# ESP32.net
KiCad netlist of a schematic drawn in Altium Designer
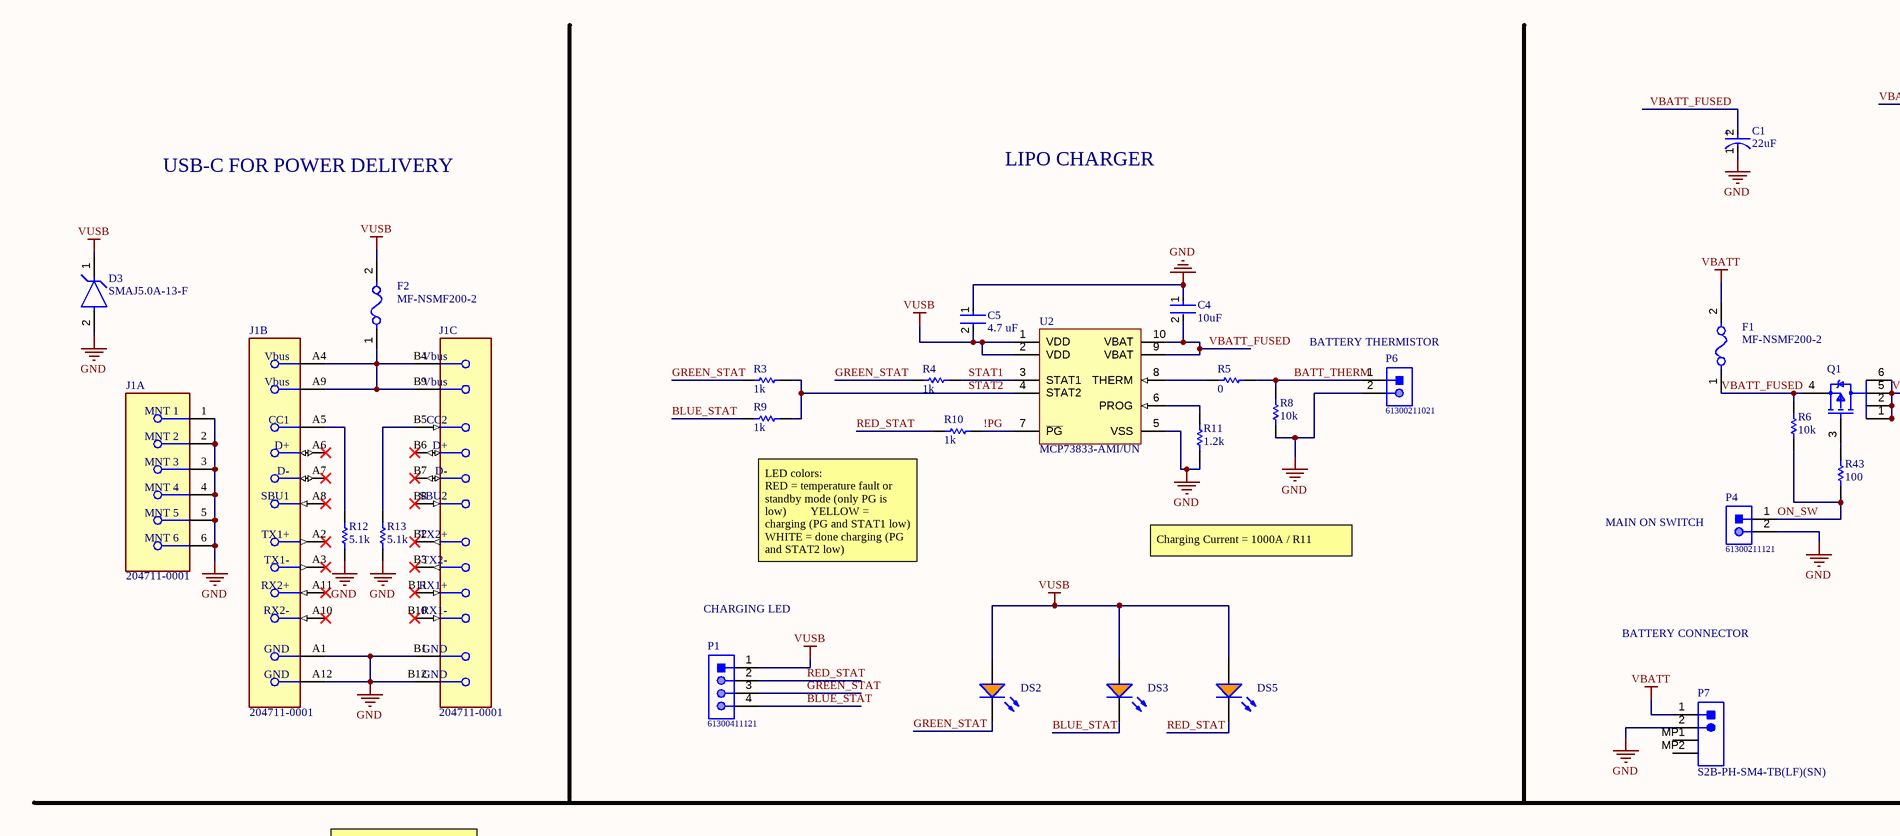
[diagram p0: ESP32.SchDoc, top left]
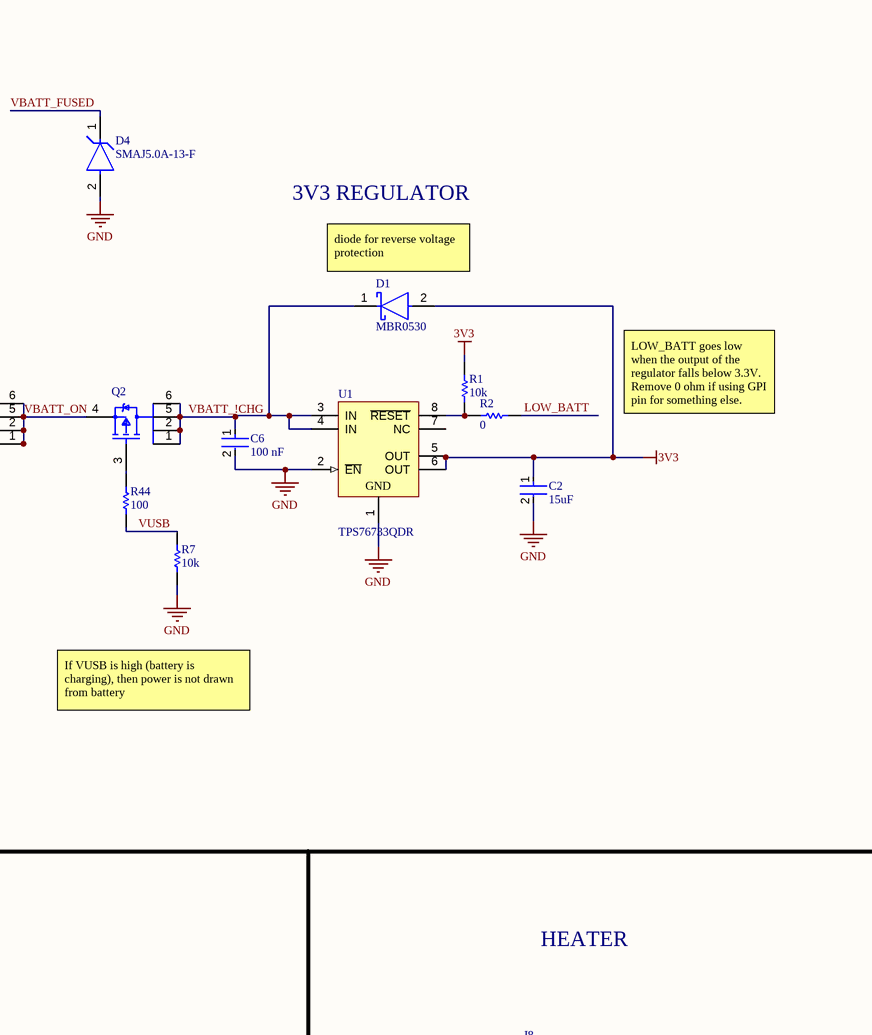
[diagram p1: ESP32.SchDoc, top right]
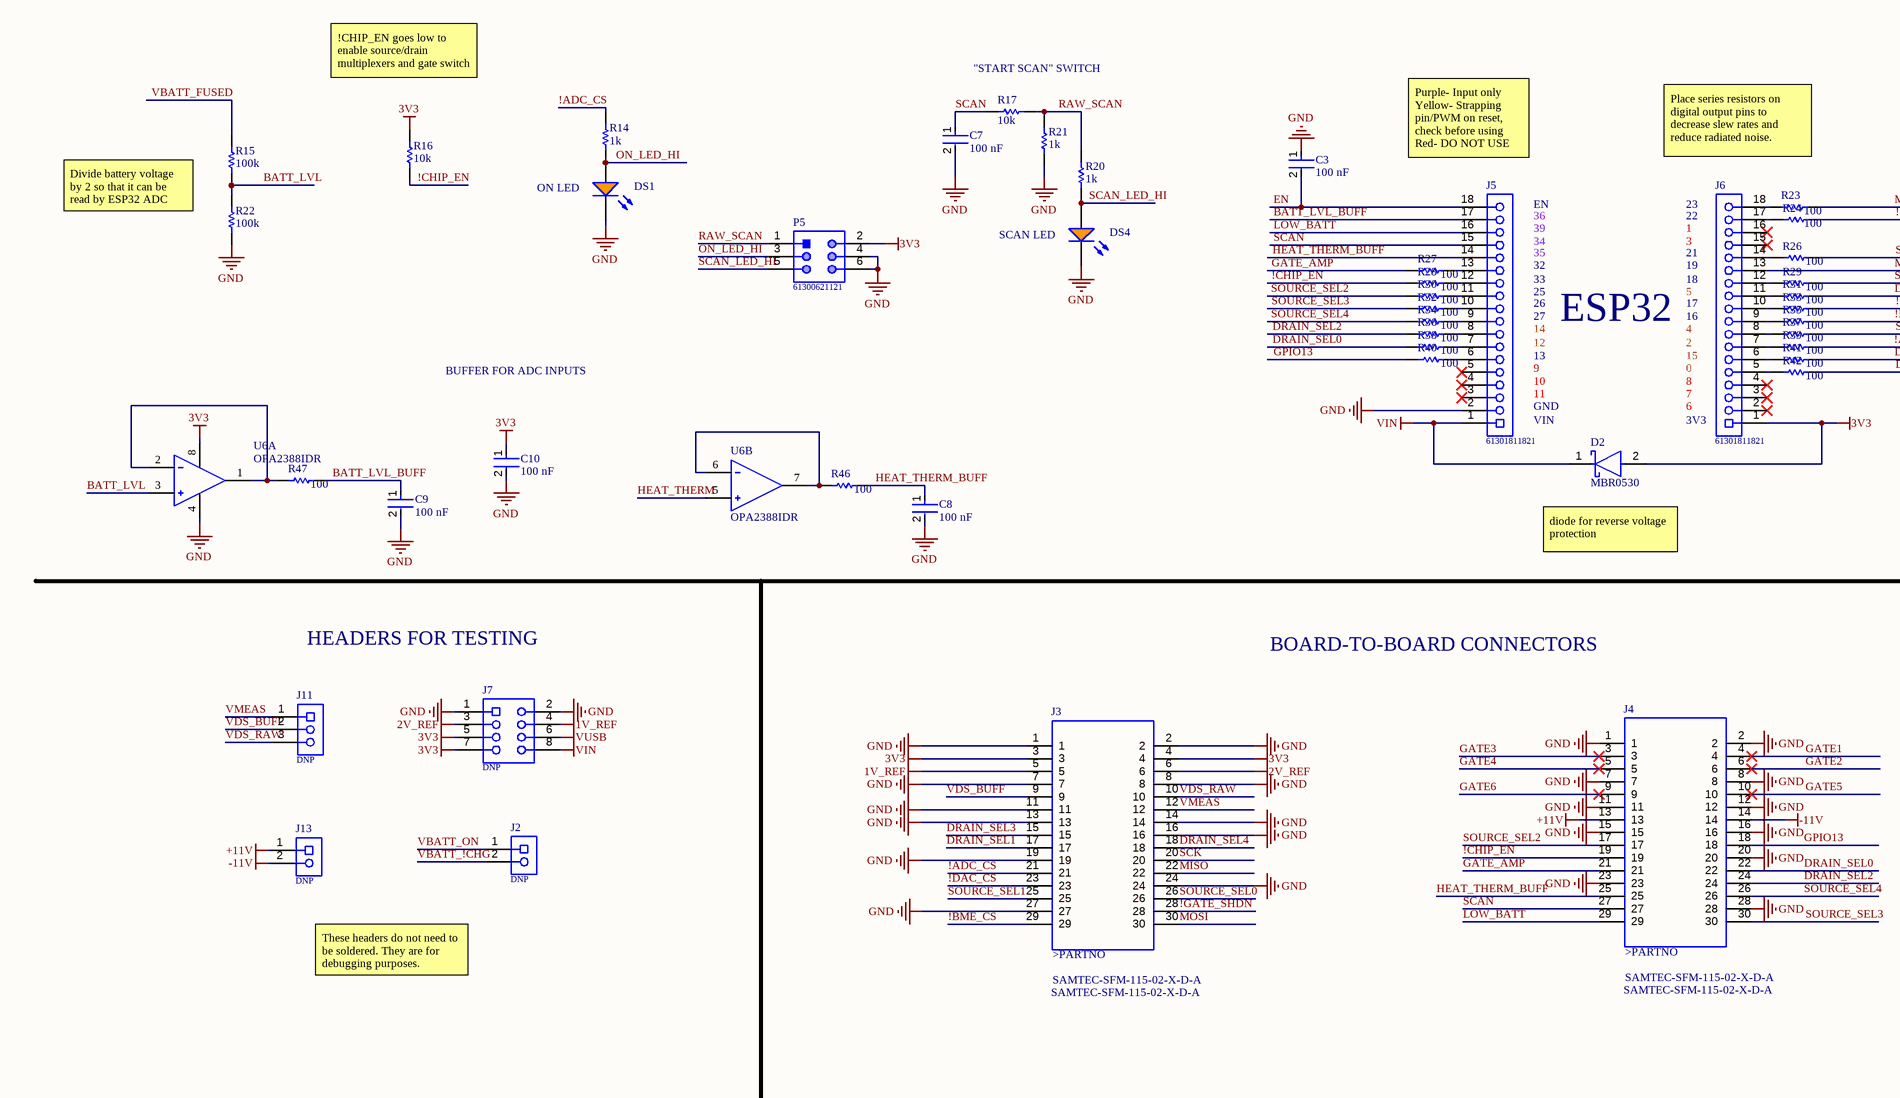
[diagram p2: ESP32.SchDoc, bottom left]
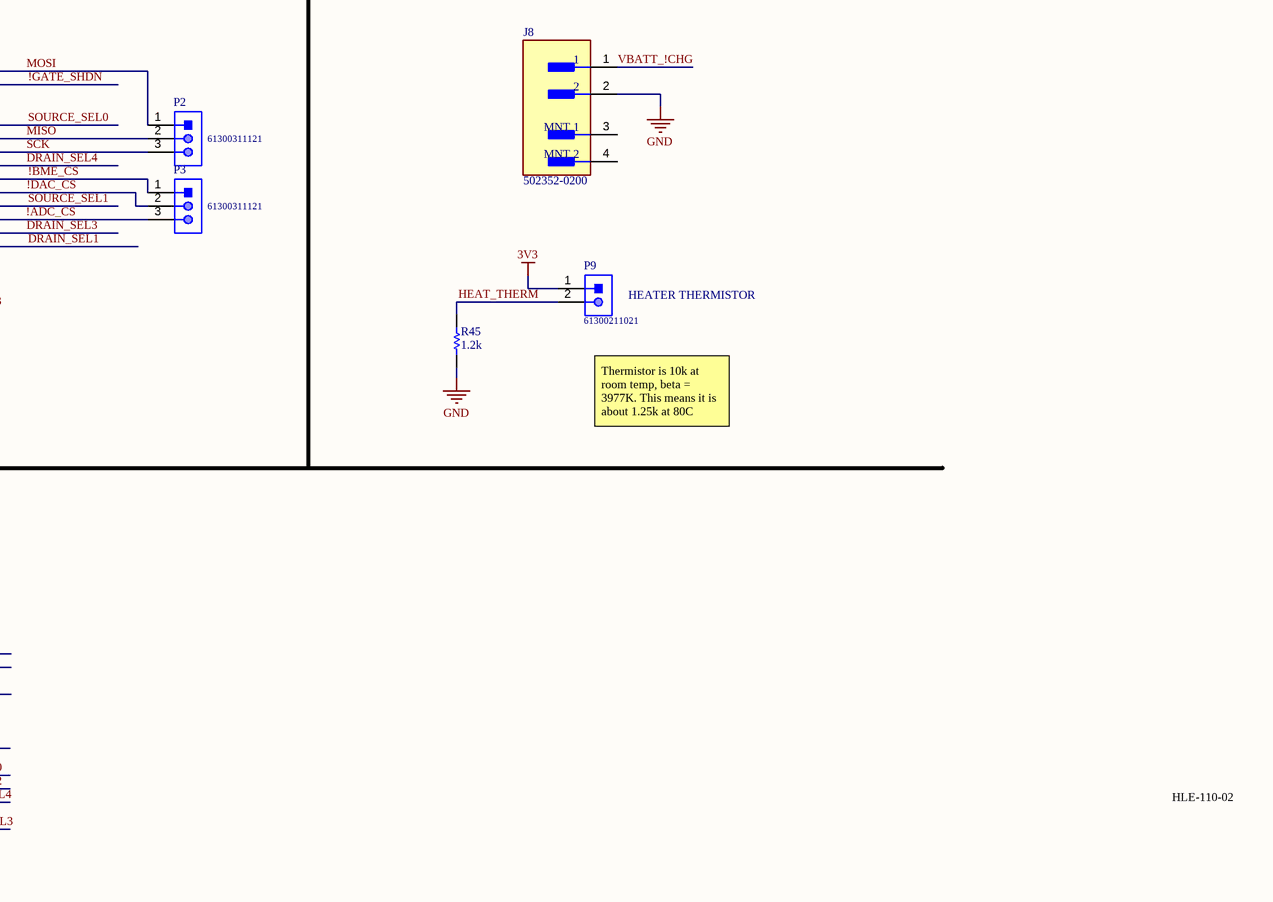
[diagram p3: ESP32.SchDoc, bottom right]

(export (version "E")
  (design (tool "Eeschema 10.0.6"))
  (components
    (comp (ref "C1")
      (value "22uF")
      (footprint "FP-FKC-MFG")
      (description "CAP ALUM 22UF 20% 35V SMD")
      (fields (field (name "VOLTAGE") "35V") (field (name "TOLERANCE") "20%"))
      (libsource (lib "Altium Content Vault") (part "a00bbbee19879c290e62620ae7e47b1"))
    )
    (comp (ref "C2")
      (value "15uF")
      (footprint "FP-C2012-125-0_2-MFG")
      (description "Multilayer Ceramic Capacitors 15μF ±20% 25V JB SMD 0805")
      (fields (field (name "TOLERANCE") "20%"))
      (libsource (lib "Altium Content Vault") (part "b4654b650e69147ec39a6b967a45e02"))
    )
    (comp (ref "C3")
      (value "100 nF")
      (footprint "FP-C0805C-DN-MFG")
      (description "CAP CER 0.1UF 50V X7R 0805")
      (fields
        (field (name "MANUFACTURER PART NUMBER") "C0805C104K5RACTU")
        (field (name "MANUFACTURER") "KEMET")
      )
      (libsource (lib "Altium Content Vault") (part "b4654b650e69147ec39a6b967a45e02"))
    )
    (comp (ref "C4")
      (value "10uF")
      (footprint "FP-GRM21B-0_1-IPC_C")
      (description "Chip Multilayer Ceramic Capacitors for General Purpose, 0805, 10uF, X5R, 15%, 10%, 16V")
      (fields (field (name "TOLERANCE") "10%") (field (name "VOLTAGE") "16V"))
      (libsource (lib "Altium Content Vault") (part "b4654b650e69147ec39a6b967a45e02"))
    )
    (comp (ref "C5")
      (value "4.7 uF")
      (footprint "FP-C0805C475K3PACTU-MFG")
      (description "CAP CER 4.7UF 25V X5R 0805")
      (fields (field (name "TOLERANCE") "10%") (field (name "VOLTAGE") "25V"))
      (libsource (lib "Altium Content Vault") (part "02cd4be3c70576c341d710602a673aa"))
    )
    (comp (ref "C6")
      (value "100 nF")
      (footprint "FP-C0805C-DN-MFG")
      (description "CAP CER 0.1UF 50V X7R 0805")
      (fields
        (field (name "MANUFACTURER PART NUMBER") "C0805C104K5RACTU")
        (field (name "MANUFACTURER") "KEMET")
      )
      (libsource (lib "Altium Content Vault") (part "b4654b650e69147ec39a6b967a45e02"))
    )
    (comp (ref "C7")
      (value "100 nF")
      (footprint "FP-C0805C-DN-MFG")
      (description "CAP CER 0.1UF 50V X7R 0805")
      (fields
        (field (name "MANUFACTURER PART NUMBER") "C0805C104K5RACTU")
        (field (name "MANUFACTURER") "KEMET")
      )
      (libsource (lib "Altium Content Vault") (part "b4654b650e69147ec39a6b967a45e02"))
    )
    (comp (ref "C8")
      (value "100 nF")
      (footprint "FP-C0805C-DN-MFG")
      (description "CAP CER 0.1UF 50V X7R 0805")
      (fields
        (field (name "MANUFACTURER PART NUMBER") "C0805C104K5RACTU")
        (field (name "MANUFACTURER") "KEMET")
      )
      (libsource (lib "Altium Content Vault") (part "b4654b650e69147ec39a6b967a45e02"))
    )
    (comp (ref "C9")
      (value "100 nF")
      (footprint "FP-C0805C-DN-MFG")
      (description "CAP CER 0.1UF 50V X7R 0805")
      (fields
        (field (name "MANUFACTURER PART NUMBER") "C0805C104K5RACTU")
        (field (name "MANUFACTURER") "KEMET")
      )
      (libsource (lib "Altium Content Vault") (part "b4654b650e69147ec39a6b967a45e02"))
    )
    (comp (ref "C10")
      (value "100 nF")
      (footprint "FP-C0805C-DN-MFG")
      (description "CAP CER 0.1UF 50V X7R 0805")
      (fields
        (field (name "MANUFACTURER PART NUMBER") "C0805C104K5RACTU")
        (field (name "MANUFACTURER") "KEMET")
      )
      (libsource (lib "Altium Content Vault") (part "b4654b650e69147ec39a6b967a45e02"))
    )
    (comp (ref "D1")
      (value "MBR0530")
      (footprint "FP-425-04-MFG")
      (description "DIODE SCHOTTKY 30V 500MA SOD123")
      (libsource (lib "Altium Content Vault") (part "1d6ec82d83fb6aee721767c19dac4b9"))
    )
    (comp (ref "D2")
      (value "MBR0530")
      (footprint "FP-425-04-MFG")
      (description "DIODE SCHOTTKY 30V 500MA SOD123")
      (libsource (lib "Altium Content Vault") (part "1d6ec82d83fb6aee721767c19dac4b9"))
    )
    (comp (ref "D3")
      (value "SMAJ5.0A-13-F")
      (footprint "FP-SMA-MFG")
      (description "TVS DIODE 5V 9.2V SMA")
      (fields
        (field (name "MANUFACTURER") "Diodes Inc.")
        (field (name "OCTOPART") "https://octopart.com/smaj5.0a-13-f-diodes+inc.-350158")
      )
      (libsource (lib "Altium Content Vault") (part "f813f71cba58e380607f5dd3caf9714"))
    )
    (comp (ref "D4")
      (value "SMAJ5.0A-13-F")
      (footprint "FP-SMA-MFG")
      (description "TVS DIODE 5V 9.2V SMA")
      (fields
        (field (name "MANUFACTURER") "Diodes Inc.")
        (field (name "OCTOPART") "https://octopart.com/smaj5.0a-13-f-diodes+inc.-350158")
      )
      (libsource (lib "Altium Content Vault") (part "f813f71cba58e380607f5dd3caf9714"))
    )
    (comp (ref "DS1")
      (value "HSMD-C170")
      (footprint "AVAG-HSMX-C170_V")
      (description "LED Uni-Color Orange, 52 mW, 20 mA, -40 to 85 degC, 2-Pin SMD, RoHS, Tape and Reel")
      (fields (field (name "MANUFACTURER") "Avago"))
      (libsource (lib "Altium Content Vault") (part "LED-ORANGE-AK-2"))
    )
    (comp (ref "DS2")
      (value "HSMD-C170")
      (footprint "AVAG-HSMX-C170_V")
      (description "LED Uni-Color Orange, 52 mW, 20 mA, -40 to 85 degC, 2-Pin SMD, RoHS, Tape and Reel")
      (fields (field (name "MANUFACTURER") "Avago"))
      (libsource (lib "Altium Content Vault") (part "LED-ORANGE-AK-2"))
    )
    (comp (ref "DS3")
      (value "HSMD-C170")
      (footprint "AVAG-HSMX-C170_V")
      (description "LED Uni-Color Orange, 52 mW, 20 mA, -40 to 85 degC, 2-Pin SMD, RoHS, Tape and Reel")
      (fields (field (name "MANUFACTURER") "Avago"))
      (libsource (lib "Altium Content Vault") (part "LED-ORANGE-AK-2"))
    )
    (comp (ref "DS4")
      (value "HSMD-C170")
      (footprint "AVAG-HSMX-C170_V")
      (description "LED Uni-Color Orange, 52 mW, 20 mA, -40 to 85 degC, 2-Pin SMD, RoHS, Tape and Reel")
      (fields (field (name "MANUFACTURER") "Avago"))
      (libsource (lib "Altium Content Vault") (part "LED-ORANGE-AK-2"))
    )
    (comp (ref "DS5")
      (value "HSMD-C170")
      (footprint "AVAG-HSMX-C170_V")
      (description "LED Uni-Color Orange, 52 mW, 20 mA, -40 to 85 degC, 2-Pin SMD, RoHS, Tape and Reel")
      (fields (field (name "MANUFACTURER") "Avago"))
      (libsource (lib "Altium Content Vault") (part "LED-ORANGE-AK-2"))
    )
    (comp (ref "F1")
      (value "MF-NSMF200-2")
      (footprint "FP-MF-NSMF200-2-MFG")
      (description "PTC RESET FUSE 6V 2A 1206")
      (fields
        (field (name "MANUFACTURER") "Bourns Inc.")
        (field (name "OCTOPART") "https://octopart.com/mf-nsmf200-2-bourns-90790")
      )
      (libsource (lib "Altium Content Vault") (part "5bcf9b9f640e542cf0359d10258e979"))
    )
    (comp (ref "F2")
      (value "MF-NSMF200-2")
      (footprint "FP-MF-NSMF200-2-MFG")
      (description "PTC RESET FUSE 6V 2A 1206")
      (fields
        (field (name "MANUFACTURER") "Bourns Inc.")
        (field (name "OCTOPART") "https://octopart.com/mf-nsmf200-2-bourns-90790")
      )
      (libsource (lib "Altium Content Vault") (part "5bcf9b9f640e542cf0359d10258e979"))
    )
    (comp (ref "J1")
      (value "204711-0001")
      (footprint "FP-204711-0001-MFG")
      (description "USB VERTICAL TYPE C 3.1")
      (libsource (lib "Altium Content Vault") (part "b295db2379a271355c8cebff2fed634"))
    )
    (comp (ref "J2")
      (value "DNP")
      (footprint "61300211821")
      (description "THT Vertical Socket Header WR-PHD, Pitch 2.54 mm, Single Row, 2 pins")
      (fields
        (field (name "PART NUMBER") "61300211821")
        (field (name "MANUFACTURER") "Wurth Elektronik")
        (field (name "PUBLISHER") "WurthElektronik")
      )
      (libsource (lib "Altium Content Vault") (part "WE-CN-1P-F-R2"))
    )
    (comp (ref "J3")
      (value "SAMTEC-SFM-115-02-X-D-A")
      (footprint "SAMTEC-SFM-115-02-X-D-A:SAMTEC-SFM-115-02-X-D-A")
      (fields (field (name "MF") "Samtec Inc."))
      (libsource (lib "SAMTEC-SFM-115-02-X-D-A") (part "SAMTEC-SFM-115-02-X-D-A"))
    )
    (comp (ref "J4")
      (value "SAMTEC-SFM-115-02-X-D-A")
      (footprint "SAMTEC-SFM-115-02-X-D-A:SAMTEC-SFM-115-02-X-D-A")
      (fields (field (name "MF") "Samtec Inc."))
      (libsource (lib "SAMTEC-SFM-115-02-X-D-A") (part "SAMTEC-SFM-115-02-X-D-A"))
    )
    (comp (ref "J5")
      (value "61301811821")
      (footprint "61301811821")
      (description "THT Vertical Socket Header WR-PHD, Pitch 2.54 mm, Single Row, 18 pins")
      (fields (field (name "MANUFACTURER") "Wurth Elektronik") (field (name "PUBLISHER") "WurthElektronik"))
      (libsource (lib "Altium Content Vault") (part "WE-CN-1P-F-R18"))
    )
    (comp (ref "J6")
      (value "61301811821")
      (footprint "61301811821")
      (description "THT Vertical Socket Header WR-PHD, Pitch 2.54 mm, Single Row, 18 pins")
      (fields (field (name "MANUFACTURER") "Wurth Elektronik") (field (name "PUBLISHER") "WurthElektronik"))
      (libsource (lib "") (part "WE-CN-1P-F-R18_1"))
    )
    (comp (ref "J7")
      (value "DNP")
      (footprint "61300821821")
      (description "THT Vertical Socket Header WR-PHD, Pitch 2.54 mm, Dual Row, 8 pins")
      (fields
        (field (name "MANUFACTURER") "Wurth Elektronik")
        (field (name "PART NUMBER") "61300821821")
        (field (name "PUBLISHER") "WurthElektronik")
      )
      (libsource (lib "Altium Content Vault") (part "WE-CN-2P-F-R8"))
    )
    (comp (ref "J8")
      (value "502352-0200")
      (footprint "FP-502352-0200-MFG")
      (description "CONN HEADER SMD R/A 2POS 2MM")
      (fields
        (field (name "MANUFACTURER") "Molex")
        (field (name "OCTOPART") "https://octopart.com/502352-0200-molex-9519058")
      )
      (libsource (lib "Altium Content Vault") (part "029478cb6d4f2fad0cd2a245525ee6d"))
    )
    (comp (ref "J11")
      (value "DNP")
      (footprint "61300311821")
      (description "THT Vertical Socket Header WR-PHD, Pitch 2.54 mm, Single Row, 3 pins")
      (fields
        (field (name "MANUFACTURER") "Wurth Elektronik")
        (field (name "PART NUMBER") "61300311821")
        (field (name "PUBLISHER") "WurthElektronik")
      )
      (libsource (lib "Altium Content Vault") (part "WE-CN-1P-F-R3"))
    )
    (comp (ref "J13")
      (value "DNP")
      (footprint "61300211821")
      (description "THT Vertical Socket Header WR-PHD, Pitch 2.54 mm, Single Row, 2 pins")
      (fields
        (field (name "PART NUMBER") "61300211821")
        (field (name "MANUFACTURER") "Wurth Elektronik")
        (field (name "PUBLISHER") "WurthElektronik")
      )
      (libsource (lib "Altium Content Vault") (part "WE-CN-1P-F-R2"))
    )
    (comp (ref "P1")
      (value "61300411121")
      (footprint "61300411121")
      (description "THT Vertical Pin Header WR-PHD, Pitch 2.54 mm, Single Row, 4 pins")
      (fields (field (name "MANUFACTURER") "Wurth Elektronik") (field (name "PUBLISHER") "WurthElektronik"))
      (libsource (lib "Altium Content Vault") (part "WE-CN-1P-M-R4"))
    )
    (comp (ref "P2")
      (value "61300311121")
      (footprint "61300311121")
      (description "THT Vertical Pin Header WR-PHD, Pitch 2.54 mm, Single Row, 3 pins")
      (fields (field (name "MANUFACTURER") "Wurth Elektronik") (field (name "PUBLISHER") "WurthElektronik"))
      (libsource (lib "Altium Content Vault") (part "WE-CN-1P-M-R3"))
    )
    (comp (ref "P3")
      (value "61300311121")
      (footprint "61300311121")
      (description "THT Vertical Pin Header WR-PHD, Pitch 2.54 mm, Single Row, 3 pins")
      (fields (field (name "MANUFACTURER") "Wurth Elektronik") (field (name "PUBLISHER") "WurthElektronik"))
      (libsource (lib "Altium Content Vault") (part "WE-CN-1P-M-R3"))
    )
    (comp (ref "P4")
      (value "61300211121")
      (footprint "61300211121")
      (description "THT Vertical Pin Header WR-PHD, Pitch 2.54 mm, Single Row, 2 pins")
      (fields (field (name "MANUFACTURER") "Wurth Elektronik") (field (name "PUBLISHER") "WurthElektronik"))
      (libsource (lib "") (part "WE-CN-1P-M-R2_1"))
    )
    (comp (ref "P5")
      (value "61300621121")
      (footprint "61300621121")
      (description "THT Vertical Pin Header WR-PHD, Pitch 2.54 mm, Dual Row, 6 pins")
      (fields (field (name "MANUFACTURER") "Wurth Elektronik") (field (name "PUBLISHER") "WurthElektronik"))
      (libsource (lib "Altium Content Vault") (part "WE-CN-2P-M-R6"))
    )
    (comp (ref "P6")
      (value "61300211021")
      (footprint "61300211021")
      (description "THT Angled Pin Header WR-PHD, Pitch 2.54 mm, Single Row, 2 pins")
      (fields (field (name "MANUFACTURER") "Wurth Elektronik") (field (name "PUBLISHER") "WurthElektronik"))
      (libsource (lib "Altium Content Vault") (part "WE-CN-1P-M-R2"))
    )
    (comp (ref "P7")
      (value "S2B-PH-SM4-TB(LF)(SN)")
      (footprint "JST- S2B-PH-SM4-TB(LF)(SN)-2_V")
      (description "Male Header, Pitch 2 mm, 1 x 2 Position, Height 5.5 mm, -25 to 85 degC, RoHS, Tape and Reel")
      (libsource (lib "Altium Content Vault") (part "CN-1P-2M-R2"))
    )
    (comp (ref "P9")
      (value "61300211021")
      (footprint "61300211021")
      (description "THT Angled Pin Header WR-PHD, Pitch 2.54 mm, Single Row, 2 pins")
      (fields (field (name "MANUFACTURER") "Wurth Elektronik") (field (name "PUBLISHER") "WurthElektronik"))
      (libsource (lib "Altium Content Vault") (part "WE-CN-1P-M-R2"))
    )
    (comp (ref "Q1")
      (value "SI3493DDV-T1-GE3")
      (footprint "FP-C-06593-MFG")
      (description "MOSFET P-CHANNEL 20V 8A 6TSOP")
      (fields
        (field (name "MANUFACTURER") "Vishay")
        (field (name "OCTOPART") "https://octopart.com/si3493ddv-t1-ge3-vishay-81014282")
      )
      (libsource (lib "Altium Content Vault") (part "cb80e2443ef6eac25cf60ecf9c1abdf"))
    )
    (comp (ref "Q2")
      (value "SI3493DDV-T1-GE3")
      (footprint "FP-C-06593-MFG")
      (description "MOSFET P-CHANNEL 20V 8A 6TSOP")
      (fields
        (field (name "MANUFACTURER") "Vishay")
        (field (name "OCTOPART") "https://octopart.com/si3493ddv-t1-ge3-vishay-81014282")
      )
      (libsource (lib "Altium Content Vault") (part "cb80e2443ef6eac25cf60ecf9c1abdf"))
    )
    (comp (ref "R1")
      (value "10k")
      (footprint "RESC2013X60X35NL10T20")
      (description "Chip Resistor, 10 KOhm, +/- 1%, 0.125 W, -55 to 155 degC, 0805 (2012 Metric), RoHS, Tape and Reel")
      (fields (field (name "MANUFACTURER") "Yageo"))
      (libsource (lib "Altium Content Vault") (part "RES-2"))
    )
    (comp (ref "R2")
      (value "0")
      (footprint "RESC2013X50X30LL20T20")
      (fields (field (name "MANUFACTURER") "Vishay Dale") (field (name "PART NUMBER") "CRCW08050000Z0EA"))
      (libsource (lib "Altium Content Vault") (part "RES"))
    )
    (comp (ref "R3")
      (value "1k")
      (footprint "RESC2013X55X40LL15T20")
      (description "TNPW08051K00BEEN")
      (fields (field (name "MANUFACTURER") "Vishay Dale"))
      (libsource (lib "Altium Content Vault") (part "RES"))
    )
    (comp (ref "R4")
      (value "1k")
      (footprint "RESC2013X55X40LL15T20")
      (description "TNPW08051K00BEEN")
      (fields (field (name "MANUFACTURER") "Vishay Dale"))
      (libsource (lib "Altium Content Vault") (part "RES"))
    )
    (comp (ref "R5")
      (value "0")
      (footprint "RESC2013X50X30LL20T20")
      (fields (field (name "MANUFACTURER") "Vishay Dale") (field (name "PART NUMBER") "CRCW08050000Z0EA"))
      (libsource (lib "Altium Content Vault") (part "RES"))
    )
    (comp (ref "R6")
      (value "10k")
      (footprint "RESC2013X60X35NL10T20")
      (description "Chip Resistor, 10 KOhm, +/- 1%, 0.125 W, -55 to 155 degC, 0805 (2012 Metric), RoHS, Tape and Reel")
      (fields (field (name "MANUFACTURER") "Yageo"))
      (libsource (lib "Altium Content Vault") (part "RES-2"))
    )
    (comp (ref "R7")
      (value "10k")
      (footprint "RESC2013X60X35NL10T20")
      (description "Chip Resistor, 10 KOhm, +/- 1%, 0.125 W, -55 to 155 degC, 0805 (2012 Metric), RoHS, Tape and Reel")
      (fields (field (name "MANUFACTURER") "Yageo"))
      (libsource (lib "Altium Content Vault") (part "RES-2"))
    )
    (comp (ref "R8")
      (value "10k")
      (footprint "RESC2013X60X35NL10T20")
      (description "Chip Resistor, 10 KOhm, +/- 1%, 0.125 W, -55 to 155 degC, 0805 (2012 Metric), RoHS, Tape and Reel")
      (fields (field (name "MANUFACTURER") "Yageo"))
      (libsource (lib "Altium Content Vault") (part "RES-2"))
    )
    (comp (ref "R9")
      (value "1k")
      (footprint "RESC2013X55X40LL15T20")
      (description "TNPW08051K00BEEN")
      (fields (field (name "MANUFACTURER") "Vishay Dale"))
      (libsource (lib "Altium Content Vault") (part "RES"))
    )
    (comp (ref "R10")
      (value "1k")
      (footprint "RESC2013X55X40LL15T20")
      (description "TNPW08051K00BEEN")
      (fields (field (name "MANUFACTURER") "Vishay Dale"))
      (libsource (lib "Altium Content Vault") (part "RES"))
    )
    (comp (ref "R11")
      (value "1.2k")
      (footprint "RESC2013X60X40LL20T25")
      (description "precision 0.1%")
      (fields (field (name "MANUFACTURER") "Panasonic") (field (name "PART NUMBER") "ERA6AEB122V"))
      (libsource (lib "Altium Content Vault") (part "RES"))
    )
    (comp (ref "R12")
      (value "5.1k")
      (footprint "RESC2013X60X40LL20T25")
      (fields (field (name "MANUFACTURER") "Panasonic") (field (name "PART NUMBER") "ERA6AEB512V"))
      (libsource (lib "Altium Content Vault") (part "RES"))
    )
    (comp (ref "R13")
      (value "5.1k")
      (footprint "RESC2013X60X40LL20T25")
      (fields (field (name "MANUFACTURER") "Panasonic") (field (name "PART NUMBER") "ERA6AEB512V"))
      (libsource (lib "Altium Content Vault") (part "RES"))
    )
    (comp (ref "R14")
      (value "1k")
      (footprint "RESC2013X55X40LL15T20")
      (description "TNPW08051K00BEEN")
      (fields (field (name "MANUFACTURER") "Vishay Dale"))
      (libsource (lib "Altium Content Vault") (part "RES"))
    )
    (comp (ref "R15")
      (value "100k")
      (footprint "RESC2013X55X40LL15T20")
      (description "precision 0.1%")
      (fields (field (name "PART NUMBER") "TNPW0805100KBEEA") (field (name "MANUFACTURER") "Vishay Dale"))
      (libsource (lib "Altium Content Vault") (part "RES"))
    )
    (comp (ref "R16")
      (value "10k")
      (footprint "RESC2013X60X35NL10T20")
      (description "Chip Resistor, 10 KOhm, +/- 1%, 0.125 W, -55 to 155 degC, 0805 (2012 Metric), RoHS, Tape and Reel")
      (fields (field (name "MANUFACTURER") "Yageo"))
      (libsource (lib "Altium Content Vault") (part "RES-2"))
    )
    (comp (ref "R17")
      (value "10k")
      (footprint "RESC2013X60X35NL10T20")
      (description "Chip Resistor, 10 KOhm, +/- 1%, 0.125 W, -55 to 155 degC, 0805 (2012 Metric), RoHS, Tape and Reel")
      (fields (field (name "MANUFACTURER") "Yageo"))
      (libsource (lib "Altium Content Vault") (part "RES-2"))
    )
    (comp (ref "R20")
      (value "1k")
      (footprint "RESC2013X55X40LL15T20")
      (description "TNPW08051K00BEEN")
      (fields (field (name "MANUFACTURER") "Vishay Dale"))
      (libsource (lib "Altium Content Vault") (part "RES"))
    )
    (comp (ref "R21")
      (value "1k")
      (footprint "RESC2013X55X40LL15T20")
      (description "TNPW08051K00BEEN")
      (fields (field (name "MANUFACTURER") "Vishay Dale"))
      (libsource (lib "Altium Content Vault") (part "RES"))
    )
    (comp (ref "R22")
      (value "100k")
      (footprint "RESC2013X55X40LL15T20")
      (description "precision 0.1%")
      (fields (field (name "PART NUMBER") "TNPW0805100KBEEA") (field (name "MANUFACTURER") "Vishay Dale"))
      (libsource (lib "Altium Content Vault") (part "RES"))
    )
    (comp (ref "R23")
      (value "100")
      (footprint "RESC2013X50X30LL20T20")
      (fields (field (name "MANUFACTURER") "Vishay Dale") (field (name "PART NUMBER") "CRCW0805100RFKEA"))
      (libsource (lib "Altium Content Vault") (part "RES"))
    )
    (comp (ref "R24")
      (value "100")
      (footprint "RESC2013X50X30LL20T20")
      (fields (field (name "MANUFACTURER") "Vishay Dale") (field (name "PART NUMBER") "CRCW0805100RFKEA"))
      (libsource (lib "Altium Content Vault") (part "RES"))
    )
    (comp (ref "R26")
      (value "100")
      (footprint "RESC2013X50X30LL20T20")
      (fields (field (name "MANUFACTURER") "Vishay Dale") (field (name "PART NUMBER") "CRCW0805100RFKEA"))
      (libsource (lib "Altium Content Vault") (part "RES"))
    )
    (comp (ref "R27")
      (value "100")
      (footprint "RESC2013X50X30LL20T20")
      (fields (field (name "MANUFACTURER") "Vishay Dale") (field (name "PART NUMBER") "CRCW0805100RFKEA"))
      (libsource (lib "Altium Content Vault") (part "RES"))
    )
    (comp (ref "R28")
      (value "100")
      (footprint "RESC2013X50X30LL20T20")
      (fields (field (name "MANUFACTURER") "Vishay Dale") (field (name "PART NUMBER") "CRCW0805100RFKEA"))
      (libsource (lib "Altium Content Vault") (part "RES"))
    )
    (comp (ref "R29")
      (value "100")
      (footprint "RESC2013X50X30LL20T20")
      (fields (field (name "MANUFACTURER") "Vishay Dale") (field (name "PART NUMBER") "CRCW0805100RFKEA"))
      (libsource (lib "Altium Content Vault") (part "RES"))
    )
    (comp (ref "R30")
      (value "100")
      (footprint "RESC2013X50X30LL20T20")
      (fields (field (name "MANUFACTURER") "Vishay Dale") (field (name "PART NUMBER") "CRCW0805100RFKEA"))
      (libsource (lib "Altium Content Vault") (part "RES"))
    )
    (comp (ref "R31")
      (value "100")
      (footprint "RESC2013X50X30LL20T20")
      (fields (field (name "MANUFACTURER") "Vishay Dale") (field (name "PART NUMBER") "CRCW0805100RFKEA"))
      (libsource (lib "Altium Content Vault") (part "RES"))
    )
    (comp (ref "R32")
      (value "100")
      (footprint "RESC2013X50X30LL20T20")
      (fields (field (name "MANUFACTURER") "Vishay Dale") (field (name "PART NUMBER") "CRCW0805100RFKEA"))
      (libsource (lib "Altium Content Vault") (part "RES"))
    )
    (comp (ref "R33")
      (value "100")
      (footprint "RESC2013X50X30LL20T20")
      (fields (field (name "MANUFACTURER") "Vishay Dale") (field (name "PART NUMBER") "CRCW0805100RFKEA"))
      (libsource (lib "Altium Content Vault") (part "RES"))
    )
    (comp (ref "R34")
      (value "100")
      (footprint "RESC2013X50X30LL20T20")
      (fields (field (name "MANUFACTURER") "Vishay Dale") (field (name "PART NUMBER") "CRCW0805100RFKEA"))
      (libsource (lib "Altium Content Vault") (part "RES"))
    )
    (comp (ref "R35")
      (value "100")
      (footprint "RESC2013X50X30LL20T20")
      (fields (field (name "MANUFACTURER") "Vishay Dale") (field (name "PART NUMBER") "CRCW0805100RFKEA"))
      (libsource (lib "Altium Content Vault") (part "RES"))
    )
    (comp (ref "R36")
      (value "100")
      (footprint "RESC2013X50X30LL20T20")
      (fields (field (name "MANUFACTURER") "Vishay Dale") (field (name "PART NUMBER") "CRCW0805100RFKEA"))
      (libsource (lib "Altium Content Vault") (part "RES"))
    )
    (comp (ref "R37")
      (value "100")
      (footprint "RESC2013X50X30LL20T20")
      (fields (field (name "MANUFACTURER") "Vishay Dale") (field (name "PART NUMBER") "CRCW0805100RFKEA"))
      (libsource (lib "Altium Content Vault") (part "RES"))
    )
    (comp (ref "R38")
      (value "100")
      (footprint "RESC2013X50X30LL20T20")
      (fields (field (name "MANUFACTURER") "Vishay Dale") (field (name "PART NUMBER") "CRCW0805100RFKEA"))
      (libsource (lib "Altium Content Vault") (part "RES"))
    )
    (comp (ref "R39")
      (value "100")
      (footprint "RESC2013X50X30LL20T20")
      (fields (field (name "MANUFACTURER") "Vishay Dale") (field (name "PART NUMBER") "CRCW0805100RFKEA"))
      (libsource (lib "Altium Content Vault") (part "RES"))
    )
    (comp (ref "R40")
      (value "100")
      (footprint "RESC2013X50X30LL20T20")
      (fields (field (name "MANUFACTURER") "Vishay Dale") (field (name "PART NUMBER") "CRCW0805100RFKEA"))
      (libsource (lib "Altium Content Vault") (part "RES"))
    )
    (comp (ref "R41")
      (value "100")
      (footprint "RESC2013X50X30LL20T20")
      (fields (field (name "MANUFACTURER") "Vishay Dale") (field (name "PART NUMBER") "CRCW0805100RFKEA"))
      (libsource (lib "Altium Content Vault") (part "RES"))
    )
    (comp (ref "R42")
      (value "100")
      (footprint "RESC2013X50X30LL20T20")
      (fields (field (name "MANUFACTURER") "Vishay Dale") (field (name "PART NUMBER") "CRCW0805100RFKEA"))
      (libsource (lib "Altium Content Vault") (part "RES"))
    )
    (comp (ref "R43")
      (value "100")
      (footprint "RESC2013X50X30LL20T20")
      (fields (field (name "MANUFACTURER") "Vishay Dale") (field (name "PART NUMBER") "CRCW0805100RFKEA"))
      (libsource (lib "Altium Content Vault") (part "RES"))
    )
    (comp (ref "R44")
      (value "100")
      (footprint "RESC2013X50X30LL20T20")
      (fields (field (name "MANUFACTURER") "Vishay Dale") (field (name "PART NUMBER") "CRCW0805100RFKEA"))
      (libsource (lib "Altium Content Vault") (part "RES"))
    )
    (comp (ref "R45")
      (value "1.2k")
      (footprint "RESC2013X60X40LL20T25")
      (description "precision 0.1%")
      (fields (field (name "MANUFACTURER") "Panasonic") (field (name "PART NUMBER") "ERA6AEB122V"))
      (libsource (lib "Altium Content Vault") (part "RES"))
    )
    (comp (ref "R46")
      (value "100")
      (footprint "RESC2013X50X30LL20T20")
      (fields (field (name "MANUFACTURER") "Vishay Dale") (field (name "PART NUMBER") "CRCW0805100RFKEA"))
      (libsource (lib "Altium Content Vault") (part "RES"))
    )
    (comp (ref "R47")
      (value "100")
      (footprint "RESC2013X50X30LL20T20")
      (fields (field (name "MANUFACTURER") "Vishay Dale") (field (name "PART NUMBER") "CRCW0805100RFKEA"))
      (libsource (lib "Altium Content Vault") (part "RES"))
    )
    (comp (ref "U1")
      (value "TPS76733QDR")
      (footprint "D0008A_M")
      (fields (field (name "MANUFACTURER") "Texas Instruments"))
      (libsource (lib "Altium Content Vault") (part "TI-TPS7XXXXD8"))
    )
    (comp (ref "U2")
      (value "MCP73833-AMI/UN")
      (footprint "MSOP-UN10_L")
      (libsource (lib "Altium Content Vault") (part "PM-BM-MCP73833-IL10"))
    )
    (comp (ref "U6")
      (value "OPA2388IDR")
      (footprint "FP-D0008A-IPC_B")
      (description "IC OPAMP ZER-DRIFT 2CIRC 8SOIC")
      (libsource (lib "Altium Content Vault") (part "e2316128466c827d7f60a2bfca9ab81"))
    )
  )
  (nets
    (net (code "1") (name "+11V") (class "Default")
      (node (ref "J13") (pin "1") (pinfunction "1_1") (pintype "passive"))
      (node (ref "J4") (pin "13") (pinfunction "13_13") (pintype "passive"))
    )
    (net (code "2") (name "-11V") (class "Default")
      (node (ref "J13") (pin "2") (pinfunction "2_2") (pintype "passive"))
      (node (ref "J4") (pin "14") (pinfunction "14_14") (pintype "passive"))
    )
    (net (code "3") (name "/!ADC_CS") (class "Default")
      (node (ref "J3") (pin "21") (pinfunction "21_21") (pintype "passive"))
      (node (ref "P3") (pin "3") (pinfunction "3_3") (pintype "passive"))
      (node (ref "R14") (pin "2") (pinfunction "2_2") (pintype "passive"))
      (node (ref "R39") (pin "2") (pinfunction "2_2") (pintype "passive"))
    )
    (net (code "4") (name "/!BME_CS") (class "Default")
      (node (ref "J3") (pin "29") (pinfunction "29_29") (pintype "passive"))
      (node (ref "P3") (pin "1") (pinfunction "1_1") (pintype "passive"))
      (node (ref "R33") (pin "2") (pinfunction "2_2") (pintype "passive"))
    )
    (net (code "5") (name "/!CHIP_EN") (class "Default")
      (node (ref "J4") (pin "19") (pinfunction "19_19") (pintype "passive"))
      (node (ref "R16") (pin "1") (pinfunction "1_1") (pintype "passive"))
      (node (ref "R28") (pin "1") (pinfunction "1_1") (pintype "passive"))
    )
    (net (code "6") (name "/!DAC_CS") (class "Default")
      (node (ref "J3") (pin "23") (pinfunction "23_23") (pintype "passive"))
      (node (ref "P3") (pin "2") (pinfunction "2_2") (pintype "passive"))
      (node (ref "R35") (pin "2") (pinfunction "2_2") (pintype "passive"))
    )
    (net (code "7") (name "/!GATE_SHDN") (class "Default")
      (node (ref "J3") (pin "28") (pinfunction "28_28") (pintype "passive"))
      (node (ref "R24") (pin "2") (pinfunction "2_2") (pintype "passive"))
    )
    (net (code "8") (name "/!PG") (class "Default")
      (node (ref "R10") (pin "2") (pinfunction "2_2") (pintype "passive"))
      (node (ref "U2") (pin "7") (pinfunction "~{PG}_7") (pintype "open_collector"))
    )
    (net (code "9") (name "/BATT_LVL") (class "Default")
      (node (ref "R15") (pin "1") (pinfunction "1_1") (pintype "passive"))
      (node (ref "R22") (pin "2") (pinfunction "2_2") (pintype "passive"))
      (node (ref "U6") (pin "3") (pinfunction "+IN_A_3") (pintype "tri_state"))
    )
    (net (code "10") (name "/BATT_LVL_BUFF") (class "Default")
      (node (ref "C9") (pin "1") (pinfunction "1_1") (pintype "passive"))
      (node (ref "J5") (pin "17") (pinfunction "17_17") (pintype "passive"))
      (node (ref "R47") (pin "2") (pinfunction "2_2") (pintype "passive"))
    )
    (net (code "11") (name "/BATT_THERM") (class "Default")
      (node (ref "P6") (pin "1") (pinfunction "1_1") (pintype "passive"))
      (node (ref "R5") (pin "2") (pinfunction "2_2") (pintype "passive"))
      (node (ref "R8") (pin "2") (pinfunction "2_2") (pintype "passive"))
    )
    (net (code "12") (name "/BLUE_STAT") (class "Default")
      (node (ref "DS3") (pin "2") (pinfunction "K_2") (pintype "passive"))
      (node (ref "P1") (pin "4") (pinfunction "4_4") (pintype "passive"))
      (node (ref "R9") (pin "1") (pinfunction "1_1") (pintype "passive"))
    )
    (net (code "13") (name "/DRAIN_SEL0") (class "Default")
      (node (ref "J4") (pin "22") (pinfunction "22_22") (pintype "passive"))
      (node (ref "R38") (pin "1") (pinfunction "1_1") (pintype "passive"))
    )
    (net (code "14") (name "/DRAIN_SEL1") (class "Default")
      (node (ref "J3") (pin "17") (pinfunction "17_17") (pintype "passive"))
      (node (ref "R42") (pin "2") (pinfunction "2_2") (pintype "passive"))
    )
    (net (code "15") (name "/DRAIN_SEL2") (class "Default")
      (node (ref "J4") (pin "24") (pinfunction "24_24") (pintype "passive"))
      (node (ref "R36") (pin "1") (pinfunction "1_1") (pintype "passive"))
    )
    (net (code "16") (name "/DRAIN_SEL3") (class "Default")
      (node (ref "J3") (pin "15") (pinfunction "15_15") (pintype "passive"))
      (node (ref "R41") (pin "2") (pinfunction "2_2") (pintype "passive"))
    )
    (net (code "17") (name "/DRAIN_SEL4") (class "Default")
      (node (ref "J3") (pin "18") (pinfunction "18_18") (pintype "passive"))
      (node (ref "R31") (pin "2") (pinfunction "2_2") (pintype "passive"))
    )
    (net (code "18") (name "/EN") (class "Default")
      (node (ref "C3") (pin "2") (pinfunction "2_2") (pintype "passive"))
      (node (ref "J5") (pin "18") (pinfunction "18_18") (pintype "passive"))
    )
    (net (code "19") (name "/GATE1") (class "Default")
      (node (ref "J4") (pin "4") (pinfunction "4_4") (pintype "passive+no_connect"))
    )
    (net (code "20") (name "/GATE2") (class "Default")
      (node (ref "J4") (pin "6") (pinfunction "6_6") (pintype "passive+no_connect"))
    )
    (net (code "21") (name "/GATE3") (class "Default")
      (node (ref "J4") (pin "3") (pinfunction "3_3") (pintype "passive+no_connect"))
    )
    (net (code "22") (name "/GATE4") (class "Default")
      (node (ref "J4") (pin "5") (pinfunction "5_5") (pintype "passive+no_connect"))
    )
    (net (code "23") (name "/GATE5") (class "Default")
      (node (ref "J4") (pin "10") (pinfunction "10_10") (pintype "passive+no_connect"))
    )
    (net (code "24") (name "/GATE6") (class "Default")
      (node (ref "J4") (pin "9") (pinfunction "9_9") (pintype "passive+no_connect"))
    )
    (net (code "25") (name "/GATE_AMP") (class "Default")
      (node (ref "J4") (pin "21") (pinfunction "21_21") (pintype "passive"))
      (node (ref "R27") (pin "1") (pinfunction "1_1") (pintype "passive"))
    )
    (net (code "26") (name "/GPIO13") (class "Default")
      (node (ref "J4") (pin "18") (pinfunction "18_18") (pintype "passive"))
      (node (ref "R40") (pin "1") (pinfunction "1_1") (pintype "passive"))
    )
    (net (code "27") (name "/GREEN_STAT") (class "Default")
      (node (ref "DS2") (pin "2") (pinfunction "K_2") (pintype "passive"))
      (node (ref "P1") (pin "3") (pinfunction "3_3") (pintype "passive"))
      (node (ref "R3") (pin "1") (pinfunction "1_1") (pintype "passive"))
      (node (ref "R4") (pin "1") (pinfunction "1_1") (pintype "passive"))
    )
    (net (code "28") (name "/HEAT_THERM") (class "Default")
      (node (ref "P9") (pin "2") (pinfunction "2_2") (pintype "passive"))
      (node (ref "R45") (pin "2") (pinfunction "2_2") (pintype "passive"))
      (node (ref "U6") (pin "5") (pinfunction "+IN_B_5") (pintype "tri_state"))
    )
    (net (code "29") (name "/HEAT_THERM_BUFF") (class "Default")
      (node (ref "C8") (pin "1") (pinfunction "1_1") (pintype "passive"))
      (node (ref "J4") (pin "25") (pinfunction "25_25") (pintype "passive"))
      (node (ref "J5") (pin "14") (pinfunction "14_14") (pintype "passive"))
      (node (ref "R46") (pin "2") (pinfunction "2_2") (pintype "passive"))
    )
    (net (code "30") (name "/LOW_BATT") (class "Default")
      (node (ref "J4") (pin "29") (pinfunction "29_29") (pintype "passive"))
      (node (ref "J5") (pin "16") (pinfunction "16_16") (pintype "passive"))
      (node (ref "R2") (pin "2") (pinfunction "2_2") (pintype "passive"))
    )
    (net (code "31") (name "/MISO") (class "Default")
      (node (ref "J3") (pin "22") (pinfunction "22_22") (pintype "passive"))
      (node (ref "J6") (pin "13") (pinfunction "13_13") (pintype "passive"))
      (node (ref "P2") (pin "2") (pinfunction "2_2") (pintype "passive"))
    )
    (net (code "32") (name "/MOSI") (class "Default")
      (node (ref "J3") (pin "30") (pinfunction "30_30") (pintype "passive"))
      (node (ref "P2") (pin "1") (pinfunction "1_1") (pintype "passive"))
      (node (ref "R23") (pin "2") (pinfunction "2_2") (pintype "passive"))
    )
    (net (code "33") (name "/ON_LED_HI") (class "Default")
      (node (ref "DS1") (pin "1") (pinfunction "A_1") (pintype "passive"))
      (node (ref "P5") (pin "3") (pinfunction "3_3") (pintype "passive"))
      (node (ref "R14") (pin "1") (pinfunction "1_1") (pintype "passive"))
    )
    (net (code "34") (name "/ON_SW") (class "Default")
      (node (ref "P4") (pin "1") (pinfunction "1_1") (pintype "passive"))
      (node (ref "R43") (pin "1") (pinfunction "1_1") (pintype "passive"))
      (node (ref "R6") (pin "2") (pinfunction "2_2") (pintype "passive"))
    )
    (net (code "35") (name "/RAW_SCAN") (class "Default")
      (node (ref "P5") (pin "1") (pinfunction "1_1") (pintype "passive"))
      (node (ref "R17") (pin "1") (pinfunction "1_1") (pintype "passive"))
      (node (ref "R20") (pin "2") (pinfunction "2_2") (pintype "passive"))
      (node (ref "R21") (pin "1") (pinfunction "1_1") (pintype "passive"))
    )
    (net (code "36") (name "/RED_STAT") (class "Default")
      (node (ref "DS5") (pin "2") (pinfunction "K_2") (pintype "passive"))
      (node (ref "P1") (pin "2") (pinfunction "2_2") (pintype "passive"))
      (node (ref "R10") (pin "1") (pinfunction "1_1") (pintype "passive"))
    )
    (net (code "37") (name "/SCAN") (class "Default")
      (node (ref "C7") (pin "1") (pinfunction "1_1") (pintype "passive"))
      (node (ref "J4") (pin "27") (pinfunction "27_27") (pintype "passive"))
      (node (ref "J5") (pin "15") (pinfunction "15_15") (pintype "passive"))
      (node (ref "R17") (pin "2") (pinfunction "2_2") (pintype "passive"))
    )
    (net (code "38") (name "/SCAN_LED_HI") (class "Default")
      (node (ref "DS4") (pin "1") (pinfunction "A_1") (pintype "passive"))
      (node (ref "P5") (pin "5") (pinfunction "5_5") (pintype "passive"))
      (node (ref "R20") (pin "1") (pinfunction "1_1") (pintype "passive"))
    )
    (net (code "39") (name "/SCK") (class "Default")
      (node (ref "J3") (pin "20") (pinfunction "20_20") (pintype "passive"))
      (node (ref "P2") (pin "3") (pinfunction "3_3") (pintype "passive"))
      (node (ref "R29") (pin "2") (pinfunction "2_2") (pintype "passive"))
    )
    (net (code "40") (name "/SOURCE_SEL0") (class "Default")
      (node (ref "J3") (pin "26") (pinfunction "26_26") (pintype "passive"))
      (node (ref "R26") (pin "2") (pinfunction "2_2") (pintype "passive"))
    )
    (net (code "41") (name "/SOURCE_SEL1") (class "Default")
      (node (ref "J3") (pin "25") (pinfunction "25_25") (pintype "passive"))
      (node (ref "R37") (pin "2") (pinfunction "2_2") (pintype "passive"))
    )
    (net (code "42") (name "/SOURCE_SEL2") (class "Default")
      (node (ref "J4") (pin "17") (pinfunction "17_17") (pintype "passive"))
      (node (ref "R30") (pin "1") (pinfunction "1_1") (pintype "passive"))
    )
    (net (code "43") (name "/SOURCE_SEL3") (class "Default")
      (node (ref "J4") (pin "30") (pinfunction "30_30") (pintype "passive"))
      (node (ref "R32") (pin "1") (pinfunction "1_1") (pintype "passive"))
    )
    (net (code "44") (name "/SOURCE_SEL4") (class "Default")
      (node (ref "J4") (pin "26") (pinfunction "26_26") (pintype "passive"))
      (node (ref "R34") (pin "1") (pinfunction "1_1") (pintype "passive"))
    )
    (net (code "45") (name "/STAT1") (class "Default")
      (node (ref "R4") (pin "2") (pinfunction "2_2") (pintype "passive"))
      (node (ref "U2") (pin "3") (pinfunction "STAT1_3") (pintype "open_collector"))
    )
    (net (code "46") (name "/STAT2") (class "Default")
      (node (ref "R3") (pin "2") (pinfunction "2_2") (pintype "passive"))
      (node (ref "R9") (pin "2") (pinfunction "2_2") (pintype "passive"))
      (node (ref "U2") (pin "4") (pinfunction "STAT2_4") (pintype "open_collector"))
    )
    (net (code "47") (name "/VBATT_!CHG") (class "Default")
      (node (ref "C6") (pin "1") (pinfunction "1_1") (pintype "passive"))
      (node (ref "D1") (pin "1") (pinfunction "C_1") (pintype "passive"))
      (node (ref "J2") (pin "2") (pinfunction "2_2") (pintype "passive"))
      (node (ref "J8") (pin "1") (pinfunction "1_1") (pintype "passive"))
      (node (ref "Q2") (pin "1") (pinfunction "D_1") (pintype "passive"))
      (node (ref "Q2") (pin "2") (pinfunction "D_2") (pintype "passive"))
      (node (ref "Q2") (pin "5") (pinfunction "D_5") (pintype "passive"))
      (node (ref "Q2") (pin "6") (pinfunction "D_6") (pintype "passive"))
      (node (ref "U1") (pin "3") (pinfunction "IN_3") (pintype "power_in"))
      (node (ref "U1") (pin "4") (pinfunction "IN_4") (pintype "power_in"))
    )
    (net (code "48") (name "/VBATT_FUSED") (class "Default")
      (node (ref "C1") (pin "2") (pinfunction "A_2") (pintype "passive"))
      (node (ref "C4") (pin "2") (pinfunction "2_2") (pintype "passive"))
      (node (ref "D4") (pin "1") (pinfunction "C_1") (pintype "passive"))
      (node (ref "F1") (pin "1") (pinfunction "1_1") (pintype "passive"))
      (node (ref "Q1") (pin "4") (pinfunction "S_4") (pintype "passive"))
      (node (ref "R15") (pin "2") (pinfunction "2_2") (pintype "passive"))
      (node (ref "R6") (pin "1") (pinfunction "1_1") (pintype "passive"))
      (node (ref "U2") (pin "10") (pinfunction "VBAT_10") (pintype "power_in"))
      (node (ref "U2") (pin "9") (pinfunction "VBAT_9") (pintype "power_in"))
    )
    (net (code "49") (name "/VBATT_ON") (class "Default")
      (node (ref "J2") (pin "1") (pinfunction "1_1") (pintype "passive"))
      (node (ref "Q1") (pin "1") (pinfunction "D_1") (pintype "passive"))
      (node (ref "Q1") (pin "2") (pinfunction "D_2") (pintype "passive"))
      (node (ref "Q1") (pin "5") (pinfunction "D_5") (pintype "passive"))
      (node (ref "Q1") (pin "6") (pinfunction "D_6") (pintype "passive"))
      (node (ref "Q2") (pin "4") (pinfunction "S_4") (pintype "passive"))
    )
    (net (code "50") (name "/VDS_BUFF") (class "Default")
      (node (ref "J11") (pin "2") (pinfunction "2_2") (pintype "passive"))
      (node (ref "J3") (pin "9") (pinfunction "9_9") (pintype "passive"))
    )
    (net (code "51") (name "/VDS_RAW") (class "Default")
      (node (ref "J11") (pin "3") (pinfunction "3_3") (pintype "passive"))
      (node (ref "J3") (pin "10") (pinfunction "10_10") (pintype "passive"))
    )
    (net (code "52") (name "/VMEAS") (class "Default")
      (node (ref "J11") (pin "1") (pinfunction "1_1") (pintype "passive"))
      (node (ref "J3") (pin "12") (pinfunction "12_12") (pintype "passive"))
    )
    (net (code "53") (name "1V_REF") (class "Default")
      (node (ref "J3") (pin "5") (pinfunction "5_5") (pintype "passive"))
      (node (ref "J7") (pin "4") (pinfunction "4_4") (pintype "passive"))
    )
    (net (code "54") (name "2V_REF") (class "Default")
      (node (ref "J3") (pin "6") (pinfunction "6_6") (pintype "passive"))
      (node (ref "J7") (pin "3") (pinfunction "3_3") (pintype "passive"))
    )
    (net (code "55") (name "3V3") (class "Default")
      (node (ref "C10") (pin "1") (pinfunction "1_1") (pintype "passive"))
      (node (ref "C2") (pin "1") (pinfunction "1_1") (pintype "passive"))
      (node (ref "D1") (pin "2") (pinfunction "A_2") (pintype "passive"))
      (node (ref "D2") (pin "2") (pinfunction "A_2") (pintype "passive"))
      (node (ref "J3") (pin "3") (pinfunction "3_3") (pintype "passive"))
      (node (ref "J3") (pin "4") (pinfunction "4_4") (pintype "passive"))
      (node (ref "J6") (pin "1") (pinfunction "1_1") (pintype "passive"))
      (node (ref "J7") (pin "5") (pinfunction "5_5") (pintype "passive"))
      (node (ref "J7") (pin "7") (pinfunction "7_7") (pintype "passive"))
      (node (ref "P5") (pin "2") (pinfunction "2_2") (pintype "passive"))
      (node (ref "P9") (pin "1") (pinfunction "1_1") (pintype "passive"))
      (node (ref "R1") (pin "2") (pinfunction "2_2") (pintype "passive"))
      (node (ref "R16") (pin "2") (pinfunction "2_2") (pintype "passive"))
      (node (ref "U1") (pin "5") (pinfunction "OUT_5") (pintype "power_in"))
      (node (ref "U1") (pin "6") (pinfunction "OUT_6") (pintype "power_in"))
      (node (ref "U6") (pin "8") (pinfunction "V+_8") (pintype "power_in"))
    )
    (net (code "56") (name "GND") (class "Default")
      (node (ref "C1") (pin "1") (pinfunction "C_1") (pintype "passive"))
      (node (ref "C10") (pin "2") (pinfunction "2_2") (pintype "passive"))
      (node (ref "C2") (pin "2") (pinfunction "2_2") (pintype "passive"))
      (node (ref "C3") (pin "1") (pinfunction "1_1") (pintype "passive"))
      (node (ref "C4") (pin "1") (pinfunction "1_1") (pintype "passive"))
      (node (ref "C5") (pin "1") (pinfunction "1_1") (pintype "passive"))
      (node (ref "C6") (pin "2") (pinfunction "2_2") (pintype "passive"))
      (node (ref "C7") (pin "2") (pinfunction "2_2") (pintype "passive"))
      (node (ref "C8") (pin "2") (pinfunction "2_2") (pintype "passive"))
      (node (ref "C9") (pin "2") (pinfunction "2_2") (pintype "passive"))
      (node (ref "D3") (pin "2") (pinfunction "A_2") (pintype "passive"))
      (node (ref "D4") (pin "2") (pinfunction "A_2") (pintype "passive"))
      (node (ref "DS1") (pin "2") (pinfunction "K_2") (pintype "passive"))
      (node (ref "DS4") (pin "2") (pinfunction "K_2") (pintype "passive"))
      (node (ref "J1") (pin "1") (pinfunction "MNT_1_1") (pintype "passive"))
      (node (ref "J1") (pin "2") (pinfunction "MNT_2_2") (pintype "passive"))
      (node (ref "J1") (pin "3") (pinfunction "MNT_3_3") (pintype "passive"))
      (node (ref "J1") (pin "4") (pinfunction "MNT_4_4") (pintype "passive"))
      (node (ref "J1") (pin "5") (pinfunction "MNT_5_5") (pintype "passive"))
      (node (ref "J1") (pin "6") (pinfunction "MNT_6_6") (pintype "passive"))
      (node (ref "J1") (pin "A1") (pinfunction "GND_A1") (pintype "power_in"))
      (node (ref "J1") (pin "A12") (pinfunction "GND_A12") (pintype "power_in"))
      (node (ref "J1") (pin "B1") (pinfunction "GND_B1") (pintype "power_in"))
      (node (ref "J1") (pin "B12") (pinfunction "GND_B12") (pintype "power_in"))
      (node (ref "J3") (pin "1") (pinfunction "1_1") (pintype "passive"))
      (node (ref "J3") (pin "11") (pinfunction "11_11") (pintype "passive"))
      (node (ref "J3") (pin "13") (pinfunction "13_13") (pintype "passive"))
      (node (ref "J3") (pin "14") (pinfunction "14_14") (pintype "passive"))
      (node (ref "J3") (pin "16") (pinfunction "16_16") (pintype "passive"))
      (node (ref "J3") (pin "19") (pinfunction "19_19") (pintype "passive"))
      (node (ref "J3") (pin "2") (pinfunction "2_2") (pintype "passive"))
      (node (ref "J3") (pin "24") (pinfunction "24_24") (pintype "passive"))
      (node (ref "J3") (pin "27") (pinfunction "27_27") (pintype "passive"))
      (node (ref "J3") (pin "7") (pinfunction "7_7") (pintype "passive"))
      (node (ref "J3") (pin "8") (pinfunction "8_8") (pintype "passive"))
      (node (ref "J4") (pin "1") (pinfunction "1_1") (pintype "passive"))
      (node (ref "J4") (pin "11") (pinfunction "11_11") (pintype "passive"))
      (node (ref "J4") (pin "12") (pinfunction "12_12") (pintype "passive"))
      (node (ref "J4") (pin "15") (pinfunction "15_15") (pintype "passive"))
      (node (ref "J4") (pin "16") (pinfunction "16_16") (pintype "passive"))
      (node (ref "J4") (pin "2") (pinfunction "2_2") (pintype "passive"))
      (node (ref "J4") (pin "20") (pinfunction "20_20") (pintype "passive"))
      (node (ref "J4") (pin "23") (pinfunction "23_23") (pintype "passive"))
      (node (ref "J4") (pin "28") (pinfunction "28_28") (pintype "passive"))
      (node (ref "J4") (pin "7") (pinfunction "7_7") (pintype "passive"))
      (node (ref "J4") (pin "8") (pinfunction "8_8") (pintype "passive"))
      (node (ref "J5") (pin "2") (pinfunction "2_2") (pintype "passive"))
      (node (ref "J7") (pin "1") (pinfunction "1_1") (pintype "passive"))
      (node (ref "J7") (pin "2") (pinfunction "2_2") (pintype "passive"))
      (node (ref "J8") (pin "2") (pinfunction "2_2") (pintype "passive"))
      (node (ref "P4") (pin "2") (pinfunction "2_2") (pintype "passive"))
      (node (ref "P5") (pin "4") (pinfunction "4_4") (pintype "passive"))
      (node (ref "P5") (pin "6") (pinfunction "6_6") (pintype "passive"))
      (node (ref "P6") (pin "2") (pinfunction "2_2") (pintype "passive"))
      (node (ref "P7") (pin "2") (pinfunction "2_2") (pintype "passive"))
      (node (ref "R11") (pin "1") (pinfunction "1_1") (pintype "passive"))
      (node (ref "R12") (pin "1") (pinfunction "1_1") (pintype "passive"))
      (node (ref "R13") (pin "1") (pinfunction "1_1") (pintype "passive"))
      (node (ref "R21") (pin "2") (pinfunction "2_2") (pintype "passive"))
      (node (ref "R22") (pin "1") (pinfunction "1_1") (pintype "passive"))
      (node (ref "R45") (pin "1") (pinfunction "1_1") (pintype "passive"))
      (node (ref "R7") (pin "1") (pinfunction "1_1") (pintype "passive"))
      (node (ref "R8") (pin "1") (pinfunction "1_1") (pintype "passive"))
      (node (ref "U1") (pin "1") (pinfunction "GND_1") (pintype "power_in"))
      (node (ref "U1") (pin "2") (pinfunction "~{EN}_2") (pintype "input"))
      (node (ref "U2") (pin "5") (pinfunction "VSS_5") (pintype "power_in"))
      (node (ref "U6") (pin "4") (pinfunction "V-_4") (pintype "power_in"))
    )
    (net (code "57") (name "Net-(F2-Pad1)") (class "Default")
      (node (ref "F2") (pin "1") (pinfunction "1_1") (pintype "passive"))
      (node (ref "J1") (pin "A4") (pinfunction "Vbus_A4") (pintype "power_in"))
      (node (ref "J1") (pin "A9") (pinfunction "Vbus_A9") (pintype "power_in"))
      (node (ref "J1") (pin "B4") (pinfunction "Vbus_B4") (pintype "power_in"))
      (node (ref "J1") (pin "B9") (pinfunction "Vbus_B9") (pintype "power_in"))
    )
    (net (code "58") (name "Net-(J1B-CC1)") (class "Default")
      (node (ref "J1") (pin "A5") (pinfunction "CC1_A5") (pintype "passive"))
      (node (ref "R12") (pin "2") (pinfunction "2_2") (pintype "passive"))
    )
    (net (code "59") (name "Net-(J1C-CC2)") (class "Default")
      (node (ref "J1") (pin "B5") (pinfunction "CC2_B5") (pintype "input"))
      (node (ref "R13") (pin "2") (pinfunction "2_2") (pintype "passive"))
    )
    (net (code "60") (name "Net-(J5-Pad6)") (class "Default")
      (node (ref "J5") (pin "6") (pinfunction "6_6") (pintype "passive"))
      (node (ref "R40") (pin "2") (pinfunction "2_2") (pintype "passive"))
    )
    (net (code "61") (name "Net-(J5-Pad7)") (class "Default")
      (node (ref "J5") (pin "7") (pinfunction "7_7") (pintype "passive"))
      (node (ref "R38") (pin "2") (pinfunction "2_2") (pintype "passive"))
    )
    (net (code "62") (name "Net-(J5-Pad8)") (class "Default")
      (node (ref "J5") (pin "8") (pinfunction "8_8") (pintype "passive"))
      (node (ref "R36") (pin "2") (pinfunction "2_2") (pintype "passive"))
    )
    (net (code "63") (name "Net-(J5-Pad9)") (class "Default")
      (node (ref "J5") (pin "9") (pinfunction "9_9") (pintype "passive"))
      (node (ref "R34") (pin "2") (pinfunction "2_2") (pintype "passive"))
    )
    (net (code "64") (name "Net-(J5-Pad10)") (class "Default")
      (node (ref "J5") (pin "10") (pinfunction "10_10") (pintype "passive"))
      (node (ref "R32") (pin "2") (pinfunction "2_2") (pintype "passive"))
    )
    (net (code "65") (name "Net-(J5-Pad11)") (class "Default")
      (node (ref "J5") (pin "11") (pinfunction "11_11") (pintype "passive"))
      (node (ref "R30") (pin "2") (pinfunction "2_2") (pintype "passive"))
    )
    (net (code "66") (name "Net-(J5-Pad12)") (class "Default")
      (node (ref "J5") (pin "12") (pinfunction "12_12") (pintype "passive"))
      (node (ref "R28") (pin "2") (pinfunction "2_2") (pintype "passive"))
    )
    (net (code "67") (name "Net-(J5-Pad13)") (class "Default")
      (node (ref "J5") (pin "13") (pinfunction "13_13") (pintype "passive"))
      (node (ref "R27") (pin "2") (pinfunction "2_2") (pintype "passive"))
    )
    (net (code "68") (name "Net-(J6-Pad5)") (class "Default")
      (node (ref "J6") (pin "5") (pinfunction "5_5") (pintype "passive"))
      (node (ref "R42") (pin "1") (pinfunction "1_1") (pintype "passive"))
    )
    (net (code "69") (name "Net-(J6-Pad6)") (class "Default")
      (node (ref "J6") (pin "6") (pinfunction "6_6") (pintype "passive"))
      (node (ref "R41") (pin "1") (pinfunction "1_1") (pintype "passive"))
    )
    (net (code "70") (name "Net-(J6-Pad7)") (class "Default")
      (node (ref "J6") (pin "7") (pinfunction "7_7") (pintype "passive"))
      (node (ref "R39") (pin "1") (pinfunction "1_1") (pintype "passive"))
    )
    (net (code "71") (name "Net-(J6-Pad8)") (class "Default")
      (node (ref "J6") (pin "8") (pinfunction "8_8") (pintype "passive"))
      (node (ref "R37") (pin "1") (pinfunction "1_1") (pintype "passive"))
    )
    (net (code "72") (name "Net-(J6-Pad9)") (class "Default")
      (node (ref "J6") (pin "9") (pinfunction "9_9") (pintype "passive"))
      (node (ref "R35") (pin "1") (pinfunction "1_1") (pintype "passive"))
    )
    (net (code "73") (name "Net-(J6-Pad10)") (class "Default")
      (node (ref "J6") (pin "10") (pinfunction "10_10") (pintype "passive"))
      (node (ref "R33") (pin "1") (pinfunction "1_1") (pintype "passive"))
    )
    (net (code "74") (name "Net-(J6-Pad11)") (class "Default")
      (node (ref "J6") (pin "11") (pinfunction "11_11") (pintype "passive"))
      (node (ref "R31") (pin "1") (pinfunction "1_1") (pintype "passive"))
    )
    (net (code "75") (name "Net-(J6-Pad12)") (class "Default")
      (node (ref "J6") (pin "12") (pinfunction "12_12") (pintype "passive"))
      (node (ref "R29") (pin "1") (pinfunction "1_1") (pintype "passive"))
    )
    (net (code "76") (name "Net-(J6-Pad14)") (class "Default")
      (node (ref "J6") (pin "14") (pinfunction "14_14") (pintype "passive"))
      (node (ref "R26") (pin "1") (pinfunction "1_1") (pintype "passive"))
    )
    (net (code "77") (name "Net-(J6-Pad17)") (class "Default")
      (node (ref "J6") (pin "17") (pinfunction "17_17") (pintype "passive"))
      (node (ref "R24") (pin "1") (pinfunction "1_1") (pintype "passive"))
    )
    (net (code "78") (name "Net-(J6-Pad18)") (class "Default")
      (node (ref "J6") (pin "18") (pinfunction "18_18") (pintype "passive"))
      (node (ref "R23") (pin "1") (pinfunction "1_1") (pintype "passive"))
    )
    (net (code "79") (name "Net-(Q1-G)") (class "Default")
      (node (ref "Q1") (pin "3") (pinfunction "G_3") (pintype "passive"))
      (node (ref "R43") (pin "2") (pinfunction "2_2") (pintype "passive"))
    )
    (net (code "80") (name "Net-(Q2-G)") (class "Default")
      (node (ref "Q2") (pin "3") (pinfunction "G_3") (pintype "passive"))
      (node (ref "R44") (pin "2") (pinfunction "2_2") (pintype "passive"))
    )
    (net (code "81") (name "Net-(U1-~{RESET})") (class "Default")
      (node (ref "R1") (pin "1") (pinfunction "1_1") (pintype "passive"))
      (node (ref "R2") (pin "1") (pinfunction "1_1") (pintype "passive"))
      (node (ref "U1") (pin "8") (pinfunction "~{RESET}_8") (pintype "tri_state"))
    )
    (net (code "82") (name "Net-(U2-PROG)") (class "Default")
      (node (ref "R11") (pin "2") (pinfunction "2_2") (pintype "passive"))
      (node (ref "U2") (pin "6") (pinfunction "PROG_6") (pintype "input"))
    )
    (net (code "83") (name "Net-(U2-THERM)") (class "Default")
      (node (ref "R5") (pin "1") (pinfunction "1_1") (pintype "passive"))
      (node (ref "U2") (pin "8") (pinfunction "THERM_8") (pintype "input"))
    )
    (net (code "84") (name "Net-(U6A--IN_A)") (class "Default")
      (node (ref "R47") (pin "1") (pinfunction "1_1") (pintype "passive"))
      (node (ref "U6") (pin "1") (pinfunction "OUT_A_1") (pintype "passive"))
      (node (ref "U6") (pin "2") (pinfunction "-IN_A_2") (pintype "tri_state"))
    )
    (net (code "85") (name "Net-(U6B--IN_B)") (class "Default")
      (node (ref "R46") (pin "1") (pinfunction "1_1") (pintype "passive"))
      (node (ref "U6") (pin "6") (pinfunction "-IN_B_6") (pintype "tri_state"))
      (node (ref "U6") (pin "7") (pinfunction "OUT_B_7") (pintype "passive"))
    )
    (net (code "86") (name "VBATT") (class "Default")
      (node (ref "F1") (pin "2") (pinfunction "2_2") (pintype "passive"))
      (node (ref "P7") (pin "1") (pinfunction "1_1") (pintype "passive"))
    )
    (net (code "87") (name "VIN") (class "Default")
      (node (ref "D2") (pin "1") (pinfunction "C_1") (pintype "passive"))
      (node (ref "J5") (pin "1") (pinfunction "1_1") (pintype "passive"))
      (node (ref "J7") (pin "8") (pinfunction "8_8") (pintype "passive"))
    )
    (net (code "88") (name "VUSB") (class "Default")
      (node (ref "C5") (pin "2") (pinfunction "2_2") (pintype "passive"))
      (node (ref "D3") (pin "1") (pinfunction "C_1") (pintype "passive"))
      (node (ref "DS2") (pin "1") (pinfunction "A_1") (pintype "passive"))
      (node (ref "DS3") (pin "1") (pinfunction "A_1") (pintype "passive"))
      (node (ref "DS5") (pin "1") (pinfunction "A_1") (pintype "passive"))
      (node (ref "F2") (pin "2") (pinfunction "2_2") (pintype "passive"))
      (node (ref "J7") (pin "6") (pinfunction "6_6") (pintype "passive"))
      (node (ref "P1") (pin "1") (pinfunction "1_1") (pintype "passive"))
      (node (ref "R44") (pin "1") (pinfunction "1_1") (pintype "passive"))
      (node (ref "R7") (pin "2") (pinfunction "2_2") (pintype "passive"))
      (node (ref "U2") (pin "1") (pinfunction "VDD_1") (pintype "power_in"))
      (node (ref "U2") (pin "2") (pinfunction "VDD_2") (pintype "power_in"))
    )
    (net (code "89") (name "unconnected-(J1B-D+-PadA6)") (class "Default")
      (node (ref "J1") (pin "A6") (pinfunction "D+_A6") (pintype "bidirectional+no_connect"))
    )
    (net (code "90") (name "unconnected-(J1B-D--PadA7)") (class "Default")
      (node (ref "J1") (pin "A7") (pinfunction "D-_A7") (pintype "bidirectional+no_connect"))
    )
    (net (code "91") (name "unconnected-(J1B-RX2+-PadA11)") (class "Default")
      (node (ref "J1") (pin "A11") (pinfunction "RX2+_A11") (pintype "input+no_connect"))
    )
    (net (code "92") (name "unconnected-(J1B-RX2--PadA10)") (class "Default")
      (node (ref "J1") (pin "A10") (pinfunction "RX2-_A10") (pintype "input+no_connect"))
    )
    (net (code "93") (name "unconnected-(J1B-SBU1-PadA8)") (class "Default")
      (node (ref "J1") (pin "A8") (pinfunction "SBU1_A8") (pintype "input+no_connect"))
    )
    (net (code "94") (name "unconnected-(J1B-TX1+-PadA2)") (class "Default")
      (node (ref "J1") (pin "A2") (pinfunction "TX1+_A2") (pintype "output+no_connect"))
    )
    (net (code "95") (name "unconnected-(J1B-TX1--PadA3)") (class "Default")
      (node (ref "J1") (pin "A3") (pinfunction "TX1-_A3") (pintype "output+no_connect"))
    )
    (net (code "96") (name "unconnected-(J1C-D+-PadB6)") (class "Default")
      (node (ref "J1") (pin "B6") (pinfunction "D+_B6") (pintype "bidirectional+no_connect"))
    )
    (net (code "97") (name "unconnected-(J1C-D--PadB7)") (class "Default")
      (node (ref "J1") (pin "B7") (pinfunction "D-_B7") (pintype "bidirectional+no_connect"))
    )
    (net (code "98") (name "unconnected-(J1C-RX1+-PadB11)") (class "Default")
      (node (ref "J1") (pin "B11") (pinfunction "RX1+_B11") (pintype "input+no_connect"))
    )
    (net (code "99") (name "unconnected-(J1C-RX1--PadB10)") (class "Default")
      (node (ref "J1") (pin "B10") (pinfunction "RX1-_B10") (pintype "input+no_connect"))
    )
    (net (code "100") (name "unconnected-(J1C-SBU2-PadB8)") (class "Default")
      (node (ref "J1") (pin "B8") (pinfunction "SBU2_B8") (pintype "input+no_connect"))
    )
    (net (code "101") (name "unconnected-(J1C-TX2+-PadB2)") (class "Default")
      (node (ref "J1") (pin "B2") (pinfunction "TX2+_B2") (pintype "output+no_connect"))
    )
    (net (code "102") (name "unconnected-(J1C-TX2--PadB3)") (class "Default")
      (node (ref "J1") (pin "B3") (pinfunction "TX2-_B3") (pintype "output+no_connect"))
    )
    (net (code "103") (name "unconnected-(J5-Pad3)") (class "Default")
      (node (ref "J5") (pin "3") (pinfunction "3_3") (pintype "passive+no_connect"))
    )
    (net (code "104") (name "unconnected-(J5-Pad4)") (class "Default")
      (node (ref "J5") (pin "4") (pinfunction "4_4") (pintype "passive+no_connect"))
    )
    (net (code "105") (name "unconnected-(J5-Pad5)") (class "Default")
      (node (ref "J5") (pin "5") (pinfunction "5_5") (pintype "passive+no_connect"))
    )
    (net (code "106") (name "unconnected-(J6-Pad2)") (class "Default")
      (node (ref "J6") (pin "2") (pinfunction "2_2") (pintype "passive+no_connect"))
    )
    (net (code "107") (name "unconnected-(J6-Pad3)") (class "Default")
      (node (ref "J6") (pin "3") (pinfunction "3_3") (pintype "passive+no_connect"))
    )
    (net (code "108") (name "unconnected-(J6-Pad4)") (class "Default")
      (node (ref "J6") (pin "4") (pinfunction "4_4") (pintype "passive+no_connect"))
    )
    (net (code "109") (name "unconnected-(J6-Pad15)") (class "Default")
      (node (ref "J6") (pin "15") (pinfunction "15_15") (pintype "passive+no_connect"))
    )
    (net (code "110") (name "unconnected-(J6-Pad16)") (class "Default")
      (node (ref "J6") (pin "16") (pinfunction "16_16") (pintype "passive+no_connect"))
    )
    (net (code "111") (name "unconnected-(J8-MNT_1-Pad3)") (class "Default")
      (node (ref "J8") (pin "3") (pinfunction "MNT_1_3") (pintype "passive"))
    )
    (net (code "112") (name "unconnected-(J8-MNT_2-Pad4)") (class "Default")
      (node (ref "J8") (pin "4") (pinfunction "MNT_2_4") (pintype "passive"))
    )
    (net (code "113") (name "unconnected-(P7-PadMP1)") (class "Default")
      (node (ref "P7") (pin "MP1") (pinfunction "MP1_MP1") (pintype "passive"))
    )
    (net (code "114") (name "unconnected-(P7-PadMP2)") (class "Default")
      (node (ref "P7") (pin "MP2") (pinfunction "MP2_MP2") (pintype "passive"))
    )
    (net (code "115") (name "unconnected-(U1-NC-Pad7)") (class "Default")
      (node (ref "U1") (pin "7") (pinfunction "NC_7") (pintype "passive"))
    )
  )
)
